# Transistor.net
KiCad netlist of a schematic drawn in Altium Designer
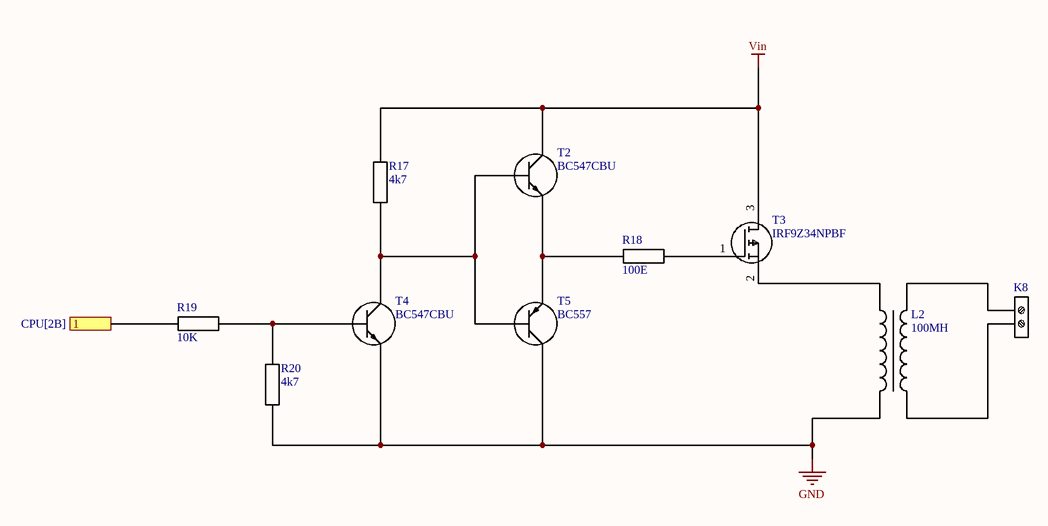
[diagram p0: Transistor.SchDoc]

(export (version "E")
  (design (tool "Eeschema 10.0.6"))
  (components
    (comp (ref "K8")
      (value "2 Pin Connector 1716020000")
      (footprint "SamacSys:1716020000")
      (description "Connector")
      (fields (field (name "MANUFACTURER_PART_NUMBER") "1716020000"))
      (libsource (lib "SamacSys") (part "2 Pin Connector 1716020000"))
    )
    (comp (ref "L2")
      (value "100MH")
      (footprint "SamacSys:CM2545X171B10")
      (description "Transformer")
      (fields (field (name "MANUFACTURER_PART_NUMBER") "CM2545X171B-10"))
      (libsource (lib "SamacSys") (part "CM2545X171B-10"))
    )
    (comp (ref "R17")
      (value "4k7")
      (footprint "0805")
      (description "Resistor")
      (fields (field (name "MANUFACTURER_PART_NUMBER") "C0805C391G3GACTU"))
      (libsource (lib "SamacSys") (part "0805 (Resistor)"))
    )
    (comp (ref "R18")
      (value "100E")
      (footprint "0805")
      (description "Resistor")
      (fields (field (name "MANUFACTURER_PART_NUMBER") "C0805C391G3GACTU"))
      (libsource (lib "SamacSys") (part "0805 (Resistor)"))
    )
    (comp (ref "R19")
      (value "10K")
      (footprint "0805")
      (description "Resistor")
      (fields (field (name "MANUFACTURER_PART_NUMBER") "C0805C391G3GACTU"))
      (libsource (lib "SamacSys") (part "0805 (Resistor)"))
    )
    (comp (ref "R20")
      (value "4k7")
      (footprint "0805")
      (description "Resistor")
      (fields (field (name "MANUFACTURER_PART_NUMBER") "C0805C391G3GACTU"))
      (libsource (lib "SamacSys") (part "0805 (Resistor)"))
    )
    (comp (ref "T2")
      (value "BC547CBU")
      (footprint "SamacSys:BC547CBU")
      (description "Transistor BJT NPN")
      (libsource (lib "SamacSys") (part "BC547CBU"))
    )
    (comp (ref "T3")
      (value "IRF9Z34NPBF")
      (footprint "SamacSys:TO254P469X1042X1967-3P")
      (description "MOSFET (P-Channel)")
      (fields (field (name "MOUSER2 PART NUMBER") "942-IRF9Z34NPBF"))
      (libsource (lib "SamacSys") (part "IRF9Z34NPBF"))
    )
    (comp (ref "T4")
      (value "BC547CBU")
      (footprint "SamacSys:BC547CBU")
      (description "Transistor BJT NPN")
      (libsource (lib "SamacSys") (part "BC547CBU"))
    )
    (comp (ref "T5")
      (value "BC557")
      (footprint "SamacSys:BC547CBU")
      (description "Transistor BJT NPN")
      (fields (field (name "MANUFACTURER_PART_NUMBER") "BC547CBU"))
      (libsource (lib "SamacSys") (part "BC557"))
    )
  )
  (nets
    (net (code "1") (name "/1") (class "Default")
      (node (ref "R19") (pin "1") (pinfunction "1_1") (pintype "passive"))
    )
    (net (code "2") (name "GND") (class "Default")
      (node (ref "L2") (pin "1") (pinfunction "PRI+_1") (pintype "passive"))
      (node (ref "R20") (pin "1") (pinfunction "1_1") (pintype "passive"))
      (node (ref "T4") (pin "3") (pinfunction "E_3") (pintype "passive"))
      (node (ref "T5") (pin "3") (pinfunction "E_3") (pintype "passive"))
    )
    (net (code "3") (name "Net-(L2-PRI-)") (class "Default")
      (node (ref "K8") (pin "2") (pinfunction "2_2") (pintype "passive"))
      (node (ref "L2") (pin "4") (pinfunction "PRI-_4") (pintype "passive"))
    )
    (net (code "4") (name "Net-(L2-SEC+)") (class "Default")
      (node (ref "L2") (pin "2") (pinfunction "SEC+_2") (pintype "passive"))
      (node (ref "T3") (pin "2") (pinfunction "S_2") (pintype "passive"))
    )
    (net (code "5") (name "Net-(L2-SEC-)") (class "Default")
      (node (ref "K8") (pin "1") (pinfunction "1_1") (pintype "passive"))
      (node (ref "L2") (pin "3") (pinfunction "SEC-_3") (pintype "passive"))
    )
    (net (code "6") (name "Net-(T2-B)") (class "Default")
      (node (ref "R17") (pin "1") (pinfunction "1_1") (pintype "passive"))
      (node (ref "T2") (pin "2") (pinfunction "B_2") (pintype "passive"))
      (node (ref "T4") (pin "1") (pinfunction "C_1") (pintype "passive"))
      (node (ref "T5") (pin "2") (pinfunction "B_2") (pintype "passive"))
    )
    (net (code "7") (name "Net-(T2-E)") (class "Default")
      (node (ref "R18") (pin "2") (pinfunction "2_2") (pintype "passive"))
      (node (ref "T2") (pin "3") (pinfunction "E_3") (pintype "passive"))
      (node (ref "T5") (pin "1") (pinfunction "C_1") (pintype "passive"))
    )
    (net (code "8") (name "Net-(T3-G)") (class "Default")
      (node (ref "R18") (pin "1") (pinfunction "1_1") (pintype "passive"))
      (node (ref "T3") (pin "1") (pinfunction "G_1") (pintype "passive"))
    )
    (net (code "9") (name "Net-(T4-B)") (class "Default")
      (node (ref "R19") (pin "2") (pinfunction "2_2") (pintype "passive"))
      (node (ref "R20") (pin "2") (pinfunction "2_2") (pintype "passive"))
      (node (ref "T4") (pin "2") (pinfunction "B_2") (pintype "passive"))
    )
    (net (code "10") (name "Vin") (class "Default")
      (node (ref "R17") (pin "2") (pinfunction "2_2") (pintype "passive"))
      (node (ref "T2") (pin "1") (pinfunction "C_1") (pintype "passive"))
      (node (ref "T3") (pin "3") (pinfunction "D_3") (pintype "passive"))
    )
  )
)
